# pulses_rev2.net
KiCad netlist of a schematic drawn in EAGLE
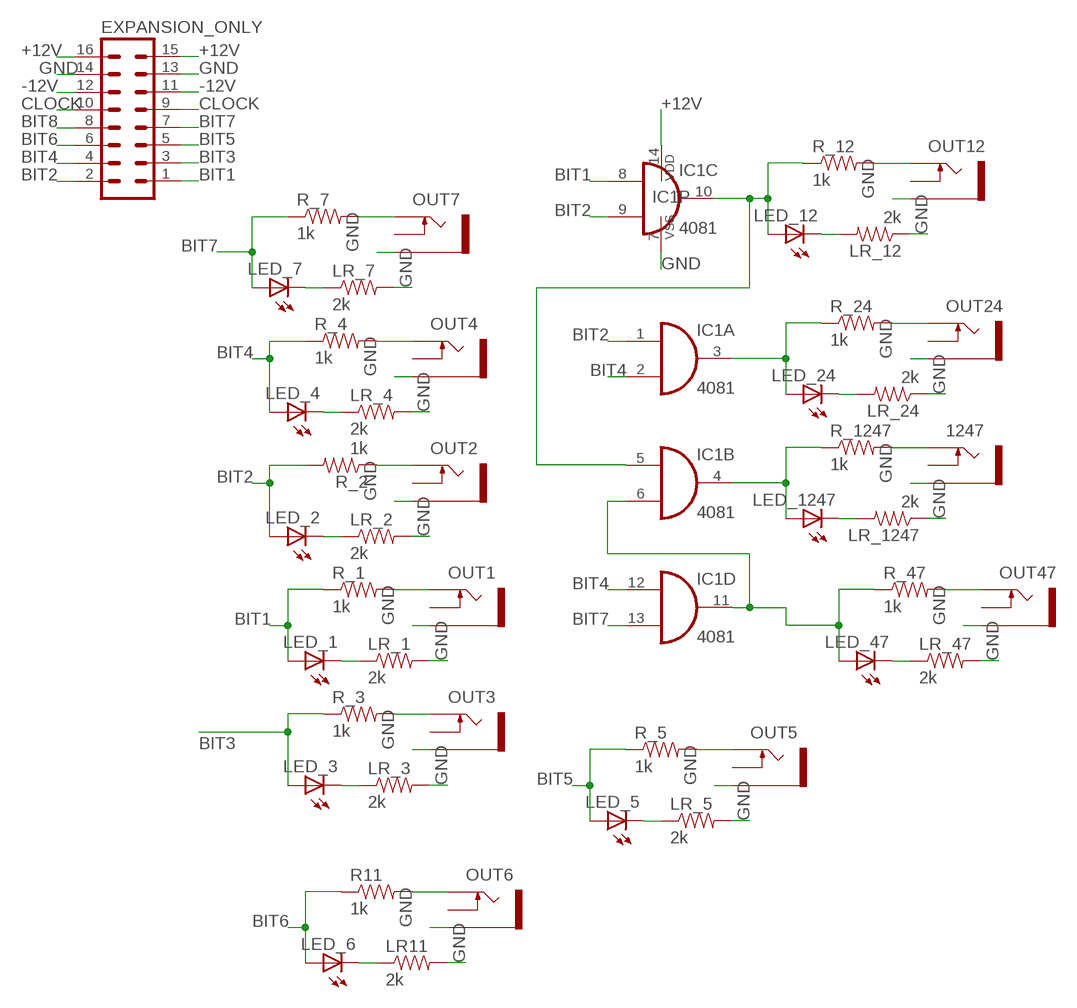
[diagram p0: schematic, sheet 1]

(export (version "E")
  (design (tool "Eeschema 10.0.6"))
  (components
    (comp (ref "1247")
      (value "THONKICONNNEW")
      (footprint "eagle-import:WQP-PJ301M-12_JACK")
      (libsource (lib "eagle-import") (part "THONKICONNNEW"))
    )
    (comp (ref "EXPANSION_ONLY")
      (value "MA08-2")
      (footprint "eagle-import:MA08-2")
      (libsource (lib "eagle-import") (part "MA08-2"))
    )
    (comp (ref "IC1")
      (value "4081")
      (footprint "eagle-import:SO14")
      (libsource (lib "eagle-import") (part "4081D"))
    )
    (comp (ref "LED_1")
      (value "LED3MM")
      (footprint "eagle-import:LED3MM")
      (libsource (lib "eagle-import") (part "LED3MM"))
    )
    (comp (ref "LED_2")
      (value "LED3MM")
      (footprint "eagle-import:LED3MM")
      (libsource (lib "eagle-import") (part "LED3MM"))
    )
    (comp (ref "LED_3")
      (value "LED3MM")
      (footprint "eagle-import:LED3MM")
      (libsource (lib "eagle-import") (part "LED3MM"))
    )
    (comp (ref "LED_4")
      (value "LED3MM")
      (footprint "eagle-import:LED3MM")
      (libsource (lib "eagle-import") (part "LED3MM"))
    )
    (comp (ref "LED_5")
      (value "LED3MM")
      (footprint "eagle-import:LED3MM")
      (libsource (lib "eagle-import") (part "LED3MM"))
    )
    (comp (ref "LED_6")
      (value "LED3MM")
      (footprint "eagle-import:LED3MM")
      (libsource (lib "eagle-import") (part "LED3MM"))
    )
    (comp (ref "LED_7")
      (value "LED3MM")
      (footprint "eagle-import:LED3MM")
      (libsource (lib "eagle-import") (part "LED3MM"))
    )
    (comp (ref "LED_12")
      (value "LED3MM")
      (footprint "eagle-import:LED3MM")
      (libsource (lib "eagle-import") (part "LED3MM"))
    )
    (comp (ref "LED_24")
      (value "LED3MM")
      (footprint "eagle-import:LED3MM")
      (libsource (lib "eagle-import") (part "LED3MM"))
    )
    (comp (ref "LED_47")
      (value "LED3MM")
      (footprint "eagle-import:LED3MM")
      (libsource (lib "eagle-import") (part "LED3MM"))
    )
    (comp (ref "LED_1247")
      (value "LED3MM")
      (footprint "eagle-import:LED3MM")
      (libsource (lib "eagle-import") (part "LED3MM"))
    )
    (comp (ref "LR11")
      (value "2k")
      (footprint "eagle-import:1206")
      (libsource (lib "eagle-import") (part "RESISTOR1206"))
    )
    (comp (ref "LR_1")
      (value "2k")
      (footprint "eagle-import:1206")
      (libsource (lib "eagle-import") (part "RESISTOR1206"))
    )
    (comp (ref "LR_2")
      (value "2k")
      (footprint "eagle-import:1206")
      (libsource (lib "eagle-import") (part "RESISTOR1206"))
    )
    (comp (ref "LR_3")
      (value "2k")
      (footprint "eagle-import:1206")
      (libsource (lib "eagle-import") (part "RESISTOR1206"))
    )
    (comp (ref "LR_4")
      (value "2k")
      (footprint "eagle-import:1206")
      (libsource (lib "eagle-import") (part "RESISTOR1206"))
    )
    (comp (ref "LR_5")
      (value "2k")
      (footprint "eagle-import:1206")
      (libsource (lib "eagle-import") (part "RESISTOR1206"))
    )
    (comp (ref "LR_7")
      (value "2k")
      (footprint "eagle-import:1206")
      (libsource (lib "eagle-import") (part "RESISTOR1206"))
    )
    (comp (ref "LR_12")
      (value "2k")
      (footprint "eagle-import:1206")
      (libsource (lib "eagle-import") (part "RESISTOR1206"))
    )
    (comp (ref "LR_24")
      (value "2k")
      (footprint "eagle-import:1206")
      (libsource (lib "eagle-import") (part "RESISTOR1206"))
    )
    (comp (ref "LR_47")
      (value "2k")
      (footprint "eagle-import:1206")
      (libsource (lib "eagle-import") (part "RESISTOR1206"))
    )
    (comp (ref "LR_1247")
      (value "2k")
      (footprint "eagle-import:1206")
      (libsource (lib "eagle-import") (part "RESISTOR1206"))
    )
    (comp (ref "OUT1")
      (value "THONKICONNNEW")
      (footprint "eagle-import:WQP-PJ301M-12_JACK")
      (libsource (lib "eagle-import") (part "THONKICONNNEW"))
    )
    (comp (ref "OUT2")
      (value "THONKICONNNEW")
      (footprint "eagle-import:WQP-PJ301M-12_JACK")
      (libsource (lib "eagle-import") (part "THONKICONNNEW"))
    )
    (comp (ref "OUT3")
      (value "THONKICONNNEW")
      (footprint "eagle-import:WQP-PJ301M-12_JACK")
      (libsource (lib "eagle-import") (part "THONKICONNNEW"))
    )
    (comp (ref "OUT4")
      (value "THONKICONNNEW")
      (footprint "eagle-import:WQP-PJ301M-12_JACK")
      (libsource (lib "eagle-import") (part "THONKICONNNEW"))
    )
    (comp (ref "OUT5")
      (value "THONKICONNNEW")
      (footprint "eagle-import:WQP-PJ301M-12_JACK")
      (libsource (lib "eagle-import") (part "THONKICONNNEW"))
    )
    (comp (ref "OUT6")
      (value "THONKICONNNEW")
      (footprint "eagle-import:WQP-PJ301M-12_JACK")
      (libsource (lib "eagle-import") (part "THONKICONNNEW"))
    )
    (comp (ref "OUT7")
      (value "THONKICONNNEW")
      (footprint "eagle-import:WQP-PJ301M-12_JACK")
      (libsource (lib "eagle-import") (part "THONKICONNNEW"))
    )
    (comp (ref "OUT12")
      (value "THONKICONNNEW")
      (footprint "eagle-import:WQP-PJ301M-12_JACK")
      (libsource (lib "eagle-import") (part "THONKICONNNEW"))
    )
    (comp (ref "OUT24")
      (value "THONKICONNNEW")
      (footprint "eagle-import:WQP-PJ301M-12_JACK")
      (libsource (lib "eagle-import") (part "THONKICONNNEW"))
    )
    (comp (ref "OUT47")
      (value "THONKICONNNEW")
      (footprint "eagle-import:WQP-PJ301M-12_JACK")
      (libsource (lib "eagle-import") (part "THONKICONNNEW"))
    )
    (comp (ref "R11")
      (value "1k")
      (footprint "eagle-import:1206")
      (libsource (lib "eagle-import") (part "RESISTOR1206"))
    )
    (comp (ref "R_1")
      (value "1k")
      (footprint "eagle-import:1206")
      (libsource (lib "eagle-import") (part "RESISTOR1206"))
    )
    (comp (ref "R_2")
      (value "1k")
      (footprint "eagle-import:1206")
      (libsource (lib "eagle-import") (part "RESISTOR1206"))
    )
    (comp (ref "R_3")
      (value "1k")
      (footprint "eagle-import:1206")
      (libsource (lib "eagle-import") (part "RESISTOR1206"))
    )
    (comp (ref "R_4")
      (value "1k")
      (footprint "eagle-import:1206")
      (libsource (lib "eagle-import") (part "RESISTOR1206"))
    )
    (comp (ref "R_5")
      (value "1k")
      (footprint "eagle-import:1206")
      (libsource (lib "eagle-import") (part "RESISTOR1206"))
    )
    (comp (ref "R_7")
      (value "1k")
      (footprint "eagle-import:1206")
      (libsource (lib "eagle-import") (part "RESISTOR1206"))
    )
    (comp (ref "R_12")
      (value "1k")
      (footprint "eagle-import:1206")
      (libsource (lib "eagle-import") (part "RESISTOR1206"))
    )
    (comp (ref "R_24")
      (value "1k")
      (footprint "eagle-import:1206")
      (libsource (lib "eagle-import") (part "RESISTOR1206"))
    )
    (comp (ref "R_47")
      (value "1k")
      (footprint "eagle-import:1206")
      (libsource (lib "eagle-import") (part "RESISTOR1206"))
    )
    (comp (ref "R_1247")
      (value "1k")
      (footprint "eagle-import:1206")
      (libsource (lib "eagle-import") (part "RESISTOR1206"))
    )
  )
  (nets
    (net (code "1") (name "/+12V") (class "Default")
      (node (ref "EXPANSION_ONLY") (pin "15") (pinfunction "15_15") (pintype "passive"))
      (node (ref "EXPANSION_ONLY") (pin "16") (pinfunction "16_16") (pintype "passive"))
      (node (ref "IC1") (pin "14") (pinfunction "VDD_14") (pintype "power_in"))
    )
    (net (code "2") (name "/-12V") (class "Default")
      (node (ref "EXPANSION_ONLY") (pin "11") (pinfunction "11_11") (pintype "passive"))
      (node (ref "EXPANSION_ONLY") (pin "12") (pinfunction "12_12") (pintype "passive"))
    )
    (net (code "3") (name "/BIT1") (class "Default")
      (node (ref "EXPANSION_ONLY") (pin "1") (pinfunction "1_1") (pintype "passive"))
      (node (ref "IC1") (pin "8") (pinfunction "I0_8") (pintype "input"))
      (node (ref "LED_1") (pin "A") (pinfunction "A_A") (pintype "passive"))
      (node (ref "R_1") (pin "1") (pinfunction "1_1") (pintype "passive"))
    )
    (net (code "4") (name "/BIT2") (class "Default")
      (node (ref "EXPANSION_ONLY") (pin "2") (pinfunction "2_2") (pintype "passive"))
      (node (ref "IC1") (pin "1") (pinfunction "I0_1") (pintype "input"))
      (node (ref "IC1") (pin "9") (pinfunction "I1_9") (pintype "input"))
      (node (ref "LED_2") (pin "A") (pinfunction "A_A") (pintype "passive"))
      (node (ref "R_2") (pin "2") (pinfunction "2_2") (pintype "passive"))
    )
    (net (code "5") (name "/BIT3") (class "Default")
      (node (ref "EXPANSION_ONLY") (pin "3") (pinfunction "3_3") (pintype "passive"))
      (node (ref "LED_3") (pin "A") (pinfunction "A_A") (pintype "passive"))
      (node (ref "R_3") (pin "1") (pinfunction "1_1") (pintype "passive"))
    )
    (net (code "6") (name "/BIT4") (class "Default")
      (node (ref "EXPANSION_ONLY") (pin "4") (pinfunction "4_4") (pintype "passive"))
      (node (ref "IC1") (pin "12") (pinfunction "I0_12") (pintype "input"))
      (node (ref "IC1") (pin "2") (pinfunction "I1_2") (pintype "input"))
      (node (ref "LED_4") (pin "A") (pinfunction "A_A") (pintype "passive"))
      (node (ref "R_4") (pin "1") (pinfunction "1_1") (pintype "passive"))
    )
    (net (code "7") (name "/BIT5") (class "Default")
      (node (ref "EXPANSION_ONLY") (pin "5") (pinfunction "5_5") (pintype "passive"))
      (node (ref "LED_5") (pin "A") (pinfunction "A_A") (pintype "passive"))
      (node (ref "R_5") (pin "1") (pinfunction "1_1") (pintype "passive"))
    )
    (net (code "8") (name "/BIT6") (class "Default")
      (node (ref "EXPANSION_ONLY") (pin "6") (pinfunction "6_6") (pintype "passive"))
      (node (ref "LED_6") (pin "A") (pinfunction "A_A") (pintype "passive"))
      (node (ref "R11") (pin "1") (pinfunction "1_1") (pintype "passive"))
    )
    (net (code "9") (name "/BIT7") (class "Default")
      (node (ref "EXPANSION_ONLY") (pin "7") (pinfunction "7_7") (pintype "passive"))
      (node (ref "IC1") (pin "13") (pinfunction "I1_13") (pintype "input"))
      (node (ref "LED_7") (pin "A") (pinfunction "A_A") (pintype "passive"))
      (node (ref "R_7") (pin "1") (pinfunction "1_1") (pintype "passive"))
    )
    (net (code "10") (name "/BIT8") (class "Default")
      (node (ref "EXPANSION_ONLY") (pin "8") (pinfunction "8_8") (pintype "passive"))
    )
    (net (code "11") (name "/CLOCK") (class "Default")
      (node (ref "EXPANSION_ONLY") (pin "10") (pinfunction "10_10") (pintype "passive"))
      (node (ref "EXPANSION_ONLY") (pin "9") (pinfunction "9_9") (pintype "passive"))
    )
    (net (code "12") (name "/GND") (class "Default")
      (node (ref "1247") (pin "P$3_SLEEVE") (pinfunction "SLEEVE_P$3_SLEEVE") (pintype "passive"))
      (node (ref "EXPANSION_ONLY") (pin "13") (pinfunction "13_13") (pintype "passive"))
      (node (ref "EXPANSION_ONLY") (pin "14") (pinfunction "14_14") (pintype "passive"))
      (node (ref "IC1") (pin "7") (pinfunction "VSS_7") (pintype "power_in"))
      (node (ref "LR11") (pin "2") (pinfunction "2_2") (pintype "passive"))
      (node (ref "LR_1") (pin "2") (pinfunction "2_2") (pintype "passive"))
      (node (ref "LR_12") (pin "1") (pinfunction "1_1") (pintype "passive"))
      (node (ref "LR_1247") (pin "1") (pinfunction "1_1") (pintype "passive"))
      (node (ref "LR_2") (pin "2") (pinfunction "2_2") (pintype "passive"))
      (node (ref "LR_24") (pin "1") (pinfunction "1_1") (pintype "passive"))
      (node (ref "LR_3") (pin "2") (pinfunction "2_2") (pintype "passive"))
      (node (ref "LR_4") (pin "2") (pinfunction "2_2") (pintype "passive"))
      (node (ref "LR_47") (pin "2") (pinfunction "2_2") (pintype "passive"))
      (node (ref "LR_5") (pin "2") (pinfunction "2_2") (pintype "passive"))
      (node (ref "LR_7") (pin "2") (pinfunction "2_2") (pintype "passive"))
      (node (ref "OUT1") (pin "P$3_SLEEVE") (pinfunction "SLEEVE_P$3_SLEEVE") (pintype "passive"))
      (node (ref "OUT12") (pin "P$3_SLEEVE") (pinfunction "SLEEVE_P$3_SLEEVE") (pintype "passive"))
      (node (ref "OUT2") (pin "P$3_SLEEVE") (pinfunction "SLEEVE_P$3_SLEEVE") (pintype "passive"))
      (node (ref "OUT24") (pin "P$3_SLEEVE") (pinfunction "SLEEVE_P$3_SLEEVE") (pintype "passive"))
      (node (ref "OUT3") (pin "P$3_SLEEVE") (pinfunction "SLEEVE_P$3_SLEEVE") (pintype "passive"))
      (node (ref "OUT4") (pin "P$3_SLEEVE") (pinfunction "SLEEVE_P$3_SLEEVE") (pintype "passive"))
      (node (ref "OUT47") (pin "P$3_SLEEVE") (pinfunction "SLEEVE_P$3_SLEEVE") (pintype "passive"))
      (node (ref "OUT5") (pin "P$3_SLEEVE") (pinfunction "SLEEVE_P$3_SLEEVE") (pintype "passive"))
      (node (ref "OUT6") (pin "P$3_SLEEVE") (pinfunction "SLEEVE_P$3_SLEEVE") (pintype "passive"))
      (node (ref "OUT7") (pin "P$3_SLEEVE") (pinfunction "SLEEVE_P$3_SLEEVE") (pintype "passive"))
    )
    (net (code "13") (name "Net-(1247-TIP)") (class "Default")
      (node (ref "1247") (pin "P$1_TIP") (pinfunction "TIP_P$1_TIP") (pintype "passive"))
      (node (ref "R_1247") (pin "2") (pinfunction "2_2") (pintype "passive"))
    )
    (net (code "14") (name "Net-(IC1A-O)") (class "Default")
      (node (ref "IC1") (pin "3") (pinfunction "O_3") (pintype "output"))
      (node (ref "LED_24") (pin "A") (pinfunction "A_A") (pintype "passive"))
      (node (ref "R_24") (pin "1") (pinfunction "1_1") (pintype "passive"))
    )
    (net (code "15") (name "Net-(IC1B-I0)") (class "Default")
      (node (ref "IC1") (pin "10") (pinfunction "O_10") (pintype "output"))
      (node (ref "IC1") (pin "5") (pinfunction "I0_5") (pintype "input"))
      (node (ref "LED_12") (pin "A") (pinfunction "A_A") (pintype "passive"))
      (node (ref "R_12") (pin "1") (pinfunction "1_1") (pintype "passive"))
    )
    (net (code "16") (name "Net-(IC1B-I1)") (class "Default")
      (node (ref "IC1") (pin "11") (pinfunction "O_11") (pintype "output"))
      (node (ref "IC1") (pin "6") (pinfunction "I1_6") (pintype "input"))
      (node (ref "LED_47") (pin "A") (pinfunction "A_A") (pintype "passive"))
      (node (ref "R_47") (pin "1") (pinfunction "1_1") (pintype "passive"))
    )
    (net (code "17") (name "Net-(IC1B-O)") (class "Default")
      (node (ref "IC1") (pin "4") (pinfunction "O_4") (pintype "output"))
      (node (ref "LED_1247") (pin "A") (pinfunction "A_A") (pintype "passive"))
      (node (ref "R_1247") (pin "1") (pinfunction "1_1") (pintype "passive"))
    )
    (net (code "18") (name "Net-(LED_1-C)") (class "Default")
      (node (ref "LED_1") (pin "K") (pinfunction "C_K") (pintype "passive"))
      (node (ref "LR_1") (pin "1") (pinfunction "1_1") (pintype "passive"))
    )
    (net (code "19") (name "Net-(LED_2-C)") (class "Default")
      (node (ref "LED_2") (pin "K") (pinfunction "C_K") (pintype "passive"))
      (node (ref "LR_2") (pin "1") (pinfunction "1_1") (pintype "passive"))
    )
    (net (code "20") (name "Net-(LED_3-C)") (class "Default")
      (node (ref "LED_3") (pin "K") (pinfunction "C_K") (pintype "passive"))
      (node (ref "LR_3") (pin "1") (pinfunction "1_1") (pintype "passive"))
    )
    (net (code "21") (name "Net-(LED_4-C)") (class "Default")
      (node (ref "LED_4") (pin "K") (pinfunction "C_K") (pintype "passive"))
      (node (ref "LR_4") (pin "1") (pinfunction "1_1") (pintype "passive"))
    )
    (net (code "22") (name "Net-(LED_5-C)") (class "Default")
      (node (ref "LED_5") (pin "K") (pinfunction "C_K") (pintype "passive"))
      (node (ref "LR_5") (pin "1") (pinfunction "1_1") (pintype "passive"))
    )
    (net (code "23") (name "Net-(LED_6-C)") (class "Default")
      (node (ref "LED_6") (pin "K") (pinfunction "C_K") (pintype "passive"))
      (node (ref "LR11") (pin "1") (pinfunction "1_1") (pintype "passive"))
    )
    (net (code "24") (name "Net-(LED_7-C)") (class "Default")
      (node (ref "LED_7") (pin "K") (pinfunction "C_K") (pintype "passive"))
      (node (ref "LR_7") (pin "1") (pinfunction "1_1") (pintype "passive"))
    )
    (net (code "25") (name "Net-(LED_12-C)") (class "Default")
      (node (ref "LED_12") (pin "K") (pinfunction "C_K") (pintype "passive"))
      (node (ref "LR_12") (pin "2") (pinfunction "2_2") (pintype "passive"))
    )
    (net (code "26") (name "Net-(LED_24-C)") (class "Default")
      (node (ref "LED_24") (pin "K") (pinfunction "C_K") (pintype "passive"))
      (node (ref "LR_24") (pin "2") (pinfunction "2_2") (pintype "passive"))
    )
    (net (code "27") (name "Net-(LED_47-C)") (class "Default")
      (node (ref "LED_47") (pin "K") (pinfunction "C_K") (pintype "passive"))
      (node (ref "LR_47") (pin "1") (pinfunction "1_1") (pintype "passive"))
    )
    (net (code "28") (name "Net-(LED_1247-C)") (class "Default")
      (node (ref "LED_1247") (pin "K") (pinfunction "C_K") (pintype "passive"))
      (node (ref "LR_1247") (pin "2") (pinfunction "2_2") (pintype "passive"))
    )
    (net (code "29") (name "Net-(OUT1-TIP)") (class "Default")
      (node (ref "OUT1") (pin "P$1_TIP") (pinfunction "TIP_P$1_TIP") (pintype "passive"))
      (node (ref "R_1") (pin "2") (pinfunction "2_2") (pintype "passive"))
    )
    (net (code "30") (name "Net-(OUT2-TIP)") (class "Default")
      (node (ref "OUT2") (pin "P$1_TIP") (pinfunction "TIP_P$1_TIP") (pintype "passive"))
      (node (ref "R_2") (pin "1") (pinfunction "1_1") (pintype "passive"))
    )
    (net (code "31") (name "Net-(OUT3-TIP)") (class "Default")
      (node (ref "OUT3") (pin "P$1_TIP") (pinfunction "TIP_P$1_TIP") (pintype "passive"))
      (node (ref "R_3") (pin "2") (pinfunction "2_2") (pintype "passive"))
    )
    (net (code "32") (name "Net-(OUT4-TIP)") (class "Default")
      (node (ref "OUT4") (pin "P$1_TIP") (pinfunction "TIP_P$1_TIP") (pintype "passive"))
      (node (ref "R_4") (pin "2") (pinfunction "2_2") (pintype "passive"))
    )
    (net (code "33") (name "Net-(OUT5-TIP)") (class "Default")
      (node (ref "OUT5") (pin "P$1_TIP") (pinfunction "TIP_P$1_TIP") (pintype "passive"))
      (node (ref "R_5") (pin "2") (pinfunction "2_2") (pintype "passive"))
    )
    (net (code "34") (name "Net-(OUT6-TIP)") (class "Default")
      (node (ref "OUT6") (pin "P$1_TIP") (pinfunction "TIP_P$1_TIP") (pintype "passive"))
      (node (ref "R11") (pin "2") (pinfunction "2_2") (pintype "passive"))
    )
    (net (code "35") (name "Net-(OUT7-TIP)") (class "Default")
      (node (ref "OUT7") (pin "P$1_TIP") (pinfunction "TIP_P$1_TIP") (pintype "passive"))
      (node (ref "R_7") (pin "2") (pinfunction "2_2") (pintype "passive"))
    )
    (net (code "36") (name "Net-(OUT12-TIP)") (class "Default")
      (node (ref "OUT12") (pin "P$1_TIP") (pinfunction "TIP_P$1_TIP") (pintype "passive"))
      (node (ref "R_12") (pin "2") (pinfunction "2_2") (pintype "passive"))
    )
    (net (code "37") (name "Net-(OUT24-TIP)") (class "Default")
      (node (ref "OUT24") (pin "P$1_TIP") (pinfunction "TIP_P$1_TIP") (pintype "passive"))
      (node (ref "R_24") (pin "2") (pinfunction "2_2") (pintype "passive"))
    )
    (net (code "38") (name "Net-(OUT47-TIP)") (class "Default")
      (node (ref "OUT47") (pin "P$1_TIP") (pinfunction "TIP_P$1_TIP") (pintype "passive"))
      (node (ref "R_47") (pin "2") (pinfunction "2_2") (pintype "passive"))
    )
    (net (code "39") (name "unconnected-(1247-SWITCH-PadP$2_SWITCH)") (class "Default")
      (node (ref "1247") (pin "P$2_SWITCH") (pinfunction "SWITCH_P$2_SWITCH") (pintype "passive"))
    )
    (net (code "40") (name "unconnected-(OUT1-SWITCH-PadP$2_SWITCH)") (class "Default")
      (node (ref "OUT1") (pin "P$2_SWITCH") (pinfunction "SWITCH_P$2_SWITCH") (pintype "passive"))
    )
    (net (code "41") (name "unconnected-(OUT2-SWITCH-PadP$2_SWITCH)") (class "Default")
      (node (ref "OUT2") (pin "P$2_SWITCH") (pinfunction "SWITCH_P$2_SWITCH") (pintype "passive"))
    )
    (net (code "42") (name "unconnected-(OUT3-SWITCH-PadP$2_SWITCH)") (class "Default")
      (node (ref "OUT3") (pin "P$2_SWITCH") (pinfunction "SWITCH_P$2_SWITCH") (pintype "passive"))
    )
    (net (code "43") (name "unconnected-(OUT4-SWITCH-PadP$2_SWITCH)") (class "Default")
      (node (ref "OUT4") (pin "P$2_SWITCH") (pinfunction "SWITCH_P$2_SWITCH") (pintype "passive"))
    )
    (net (code "44") (name "unconnected-(OUT5-SWITCH-PadP$2_SWITCH)") (class "Default")
      (node (ref "OUT5") (pin "P$2_SWITCH") (pinfunction "SWITCH_P$2_SWITCH") (pintype "passive"))
    )
    (net (code "45") (name "unconnected-(OUT6-SWITCH-PadP$2_SWITCH)") (class "Default")
      (node (ref "OUT6") (pin "P$2_SWITCH") (pinfunction "SWITCH_P$2_SWITCH") (pintype "passive"))
    )
    (net (code "46") (name "unconnected-(OUT7-SWITCH-PadP$2_SWITCH)") (class "Default")
      (node (ref "OUT7") (pin "P$2_SWITCH") (pinfunction "SWITCH_P$2_SWITCH") (pintype "passive"))
    )
    (net (code "47") (name "unconnected-(OUT12-SWITCH-PadP$2_SWITCH)") (class "Default")
      (node (ref "OUT12") (pin "P$2_SWITCH") (pinfunction "SWITCH_P$2_SWITCH") (pintype "passive"))
    )
    (net (code "48") (name "unconnected-(OUT24-SWITCH-PadP$2_SWITCH)") (class "Default")
      (node (ref "OUT24") (pin "P$2_SWITCH") (pinfunction "SWITCH_P$2_SWITCH") (pintype "passive"))
    )
    (net (code "49") (name "unconnected-(OUT47-SWITCH-PadP$2_SWITCH)") (class "Default")
      (node (ref "OUT47") (pin "P$2_SWITCH") (pinfunction "SWITCH_P$2_SWITCH") (pintype "passive"))
    )
  )
)
